# MY_beamControl_R.net
KiCad netlist of a schematic drawn in Altium Designer
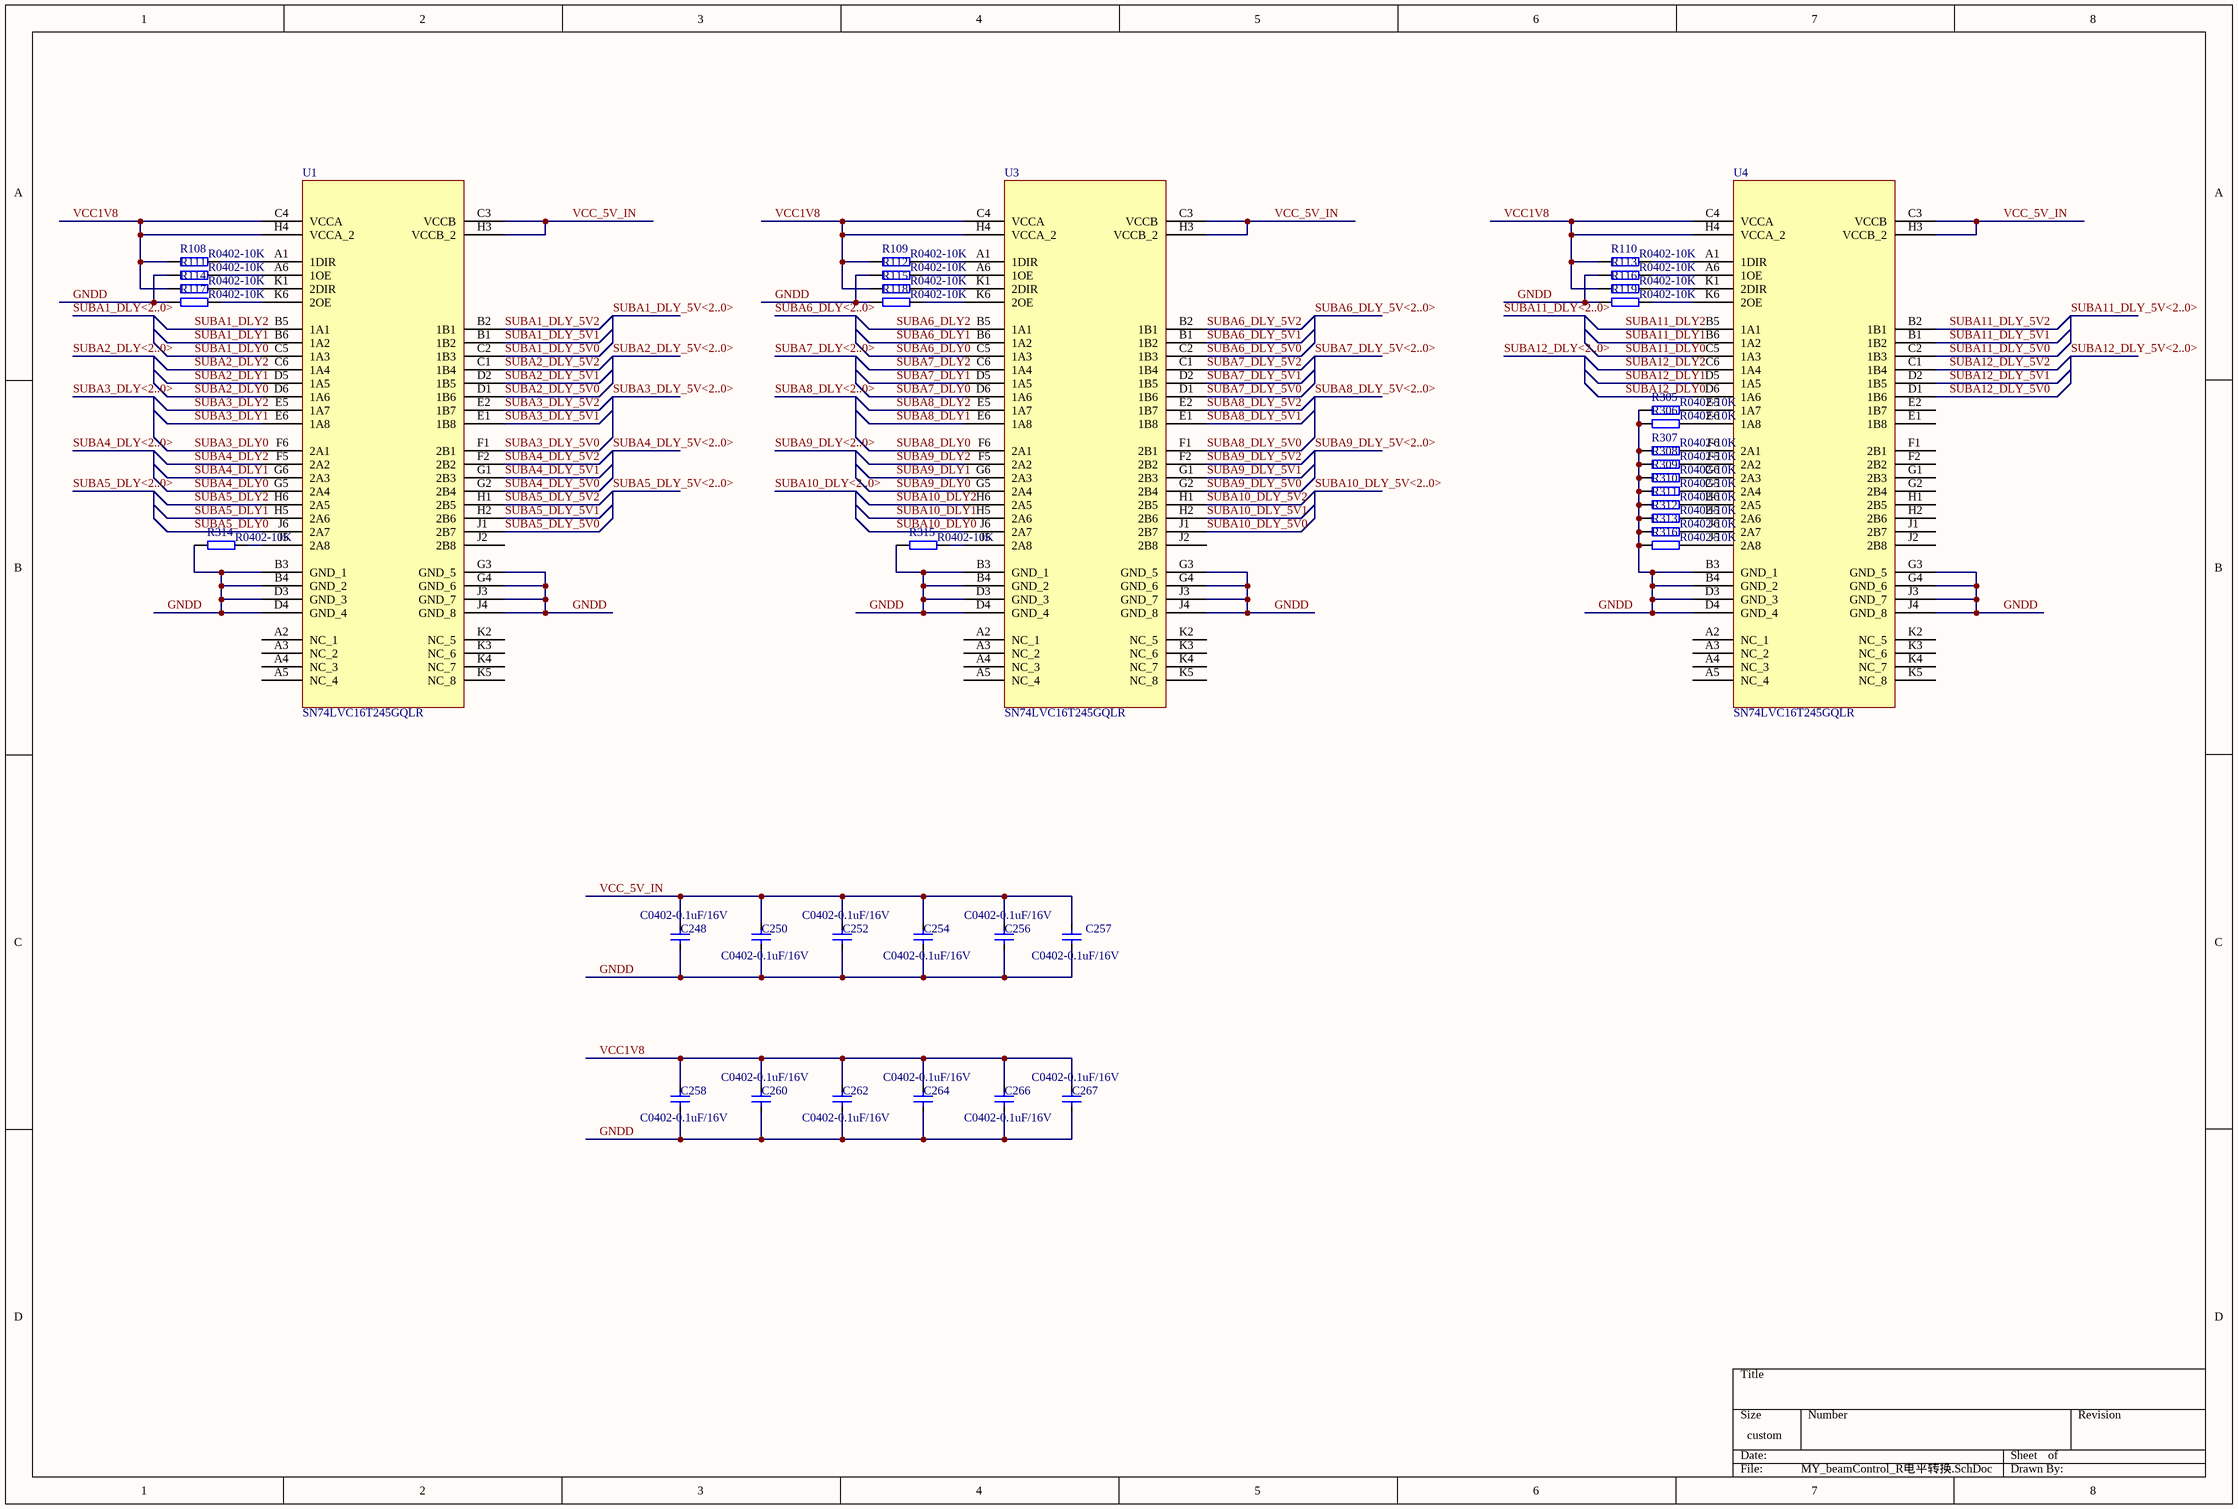
[diagram p0: MY_beamControl_R电平转换.SchDoc]

(export (version "E")
  (design (tool "Eeschema 10.0.6"))
  (components
    (comp (ref "C248")
      (value "C0402-0.1uF/16V")
      (footprint "C0402")
      (description "X7R")
      (fields (field (name "SCHEMATIC_PART") "CAP") (field (name "MANUFACTURER") "SAMSUNG"))
      (libsource (lib "Database_Libs1") (part "CAP"))
    )
    (comp (ref "C250")
      (value "C0402-0.1uF/16V")
      (footprint "C0402")
      (description "X7R")
      (fields (field (name "SCHEMATIC_PART") "CAP") (field (name "MANUFACTURER") "SAMSUNG"))
      (libsource (lib "Database_Libs1") (part "CAP"))
    )
    (comp (ref "C252")
      (value "C0402-0.1uF/16V")
      (footprint "C0402")
      (description "X7R")
      (fields (field (name "SCHEMATIC_PART") "CAP") (field (name "MANUFACTURER") "SAMSUNG"))
      (libsource (lib "Database_Libs1") (part "CAP"))
    )
    (comp (ref "C254")
      (value "C0402-0.1uF/16V")
      (footprint "C0402")
      (description "X7R")
      (fields (field (name "SCHEMATIC_PART") "CAP") (field (name "MANUFACTURER") "SAMSUNG"))
      (libsource (lib "Database_Libs1") (part "CAP"))
    )
    (comp (ref "C256")
      (value "C0402-0.1uF/16V")
      (footprint "C0402")
      (description "X7R")
      (fields (field (name "SCHEMATIC_PART") "CAP") (field (name "MANUFACTURER") "SAMSUNG"))
      (libsource (lib "Database_Libs1") (part "CAP"))
    )
    (comp (ref "C257")
      (value "C0402-0.1uF/16V")
      (footprint "C0402")
      (description "X7R")
      (fields (field (name "SCHEMATIC_PART") "CAP") (field (name "MANUFACTURER") "SAMSUNG"))
      (libsource (lib "Database_Libs1") (part "CAP"))
    )
    (comp (ref "C258")
      (value "C0402-0.1uF/16V")
      (footprint "C0402")
      (description "X7R")
      (fields (field (name "SCHEMATIC_PART") "CAP") (field (name "MANUFACTURER") "SAMSUNG"))
      (libsource (lib "Database_Libs1") (part "CAP"))
    )
    (comp (ref "C260")
      (value "C0402-0.1uF/16V")
      (footprint "C0402")
      (description "X7R")
      (fields (field (name "SCHEMATIC_PART") "CAP") (field (name "MANUFACTURER") "SAMSUNG"))
      (libsource (lib "Database_Libs1") (part "CAP"))
    )
    (comp (ref "C262")
      (value "C0402-0.1uF/16V")
      (footprint "C0402")
      (description "X7R")
      (fields (field (name "SCHEMATIC_PART") "CAP") (field (name "MANUFACTURER") "SAMSUNG"))
      (libsource (lib "Database_Libs1") (part "CAP"))
    )
    (comp (ref "C264")
      (value "C0402-0.1uF/16V")
      (footprint "C0402")
      (description "X7R")
      (fields (field (name "SCHEMATIC_PART") "CAP") (field (name "MANUFACTURER") "SAMSUNG"))
      (libsource (lib "Database_Libs1") (part "CAP"))
    )
    (comp (ref "C266")
      (value "C0402-0.1uF/16V")
      (footprint "C0402")
      (description "X7R")
      (fields (field (name "SCHEMATIC_PART") "CAP") (field (name "MANUFACTURER") "SAMSUNG"))
      (libsource (lib "Database_Libs1") (part "CAP"))
    )
    (comp (ref "C267")
      (value "C0402-0.1uF/16V")
      (footprint "C0402")
      (description "X7R")
      (fields (field (name "SCHEMATIC_PART") "CAP") (field (name "MANUFACTURER") "SAMSUNG"))
      (libsource (lib "Database_Libs1") (part "CAP"))
    )
    (comp (ref "R108")
      (value "R0402-10K")
      (footprint "R0402")
      (fields (field (name "SCHEMATIC_PART") "RES") (field (name "MANUFACTURER") "SAMSUNG"))
      (libsource (lib "Database_Libs1") (part "RES"))
    )
    (comp (ref "R109")
      (value "R0402-10K")
      (footprint "R0402")
      (fields (field (name "SCHEMATIC_PART") "RES") (field (name "MANUFACTURER") "SAMSUNG"))
      (libsource (lib "Database_Libs1") (part "RES"))
    )
    (comp (ref "R110")
      (value "R0402-10K")
      (footprint "R0402")
      (fields (field (name "SCHEMATIC_PART") "RES") (field (name "MANUFACTURER") "SAMSUNG"))
      (libsource (lib "Database_Libs1") (part "RES"))
    )
    (comp (ref "R111")
      (value "R0402-10K")
      (footprint "R0402")
      (fields (field (name "SCHEMATIC_PART") "RES") (field (name "MANUFACTURER") "SAMSUNG"))
      (libsource (lib "Database_Libs1") (part "RES"))
    )
    (comp (ref "R112")
      (value "R0402-10K")
      (footprint "R0402")
      (fields (field (name "SCHEMATIC_PART") "RES") (field (name "MANUFACTURER") "SAMSUNG"))
      (libsource (lib "Database_Libs1") (part "RES"))
    )
    (comp (ref "R113")
      (value "R0402-10K")
      (footprint "R0402")
      (fields (field (name "SCHEMATIC_PART") "RES") (field (name "MANUFACTURER") "SAMSUNG"))
      (libsource (lib "Database_Libs1") (part "RES"))
    )
    (comp (ref "R114")
      (value "R0402-10K")
      (footprint "R0402")
      (fields (field (name "SCHEMATIC_PART") "RES") (field (name "MANUFACTURER") "SAMSUNG"))
      (libsource (lib "Database_Libs1") (part "RES"))
    )
    (comp (ref "R115")
      (value "R0402-10K")
      (footprint "R0402")
      (fields (field (name "SCHEMATIC_PART") "RES") (field (name "MANUFACTURER") "SAMSUNG"))
      (libsource (lib "Database_Libs1") (part "RES"))
    )
    (comp (ref "R116")
      (value "R0402-10K")
      (footprint "R0402")
      (fields (field (name "SCHEMATIC_PART") "RES") (field (name "MANUFACTURER") "SAMSUNG"))
      (libsource (lib "Database_Libs1") (part "RES"))
    )
    (comp (ref "R117")
      (value "R0402-10K")
      (footprint "R0402")
      (fields (field (name "SCHEMATIC_PART") "RES") (field (name "MANUFACTURER") "SAMSUNG"))
      (libsource (lib "Database_Libs1") (part "RES"))
    )
    (comp (ref "R118")
      (value "R0402-10K")
      (footprint "R0402")
      (fields (field (name "SCHEMATIC_PART") "RES") (field (name "MANUFACTURER") "SAMSUNG"))
      (libsource (lib "Database_Libs1") (part "RES"))
    )
    (comp (ref "R119")
      (value "R0402-10K")
      (footprint "R0402")
      (fields (field (name "SCHEMATIC_PART") "RES") (field (name "MANUFACTURER") "SAMSUNG"))
      (libsource (lib "Database_Libs1") (part "RES"))
    )
    (comp (ref "R305")
      (value "R0402-10K")
      (footprint "R0402")
      (fields (field (name "SCHEMATIC_PART") "RES") (field (name "MANUFACTURER") "SAMSUNG"))
      (libsource (lib "Database_Libs1") (part "RES"))
    )
    (comp (ref "R306")
      (value "R0402-10K")
      (footprint "R0402")
      (fields (field (name "SCHEMATIC_PART") "RES") (field (name "MANUFACTURER") "SAMSUNG"))
      (libsource (lib "Database_Libs1") (part "RES"))
    )
    (comp (ref "R307")
      (value "R0402-10K")
      (footprint "R0402")
      (fields (field (name "SCHEMATIC_PART") "RES") (field (name "MANUFACTURER") "SAMSUNG"))
      (libsource (lib "Database_Libs1") (part "RES"))
    )
    (comp (ref "R308")
      (value "R0402-10K")
      (footprint "R0402")
      (fields (field (name "SCHEMATIC_PART") "RES") (field (name "MANUFACTURER") "SAMSUNG"))
      (libsource (lib "Database_Libs1") (part "RES"))
    )
    (comp (ref "R309")
      (value "R0402-10K")
      (footprint "R0402")
      (fields (field (name "SCHEMATIC_PART") "RES") (field (name "MANUFACTURER") "SAMSUNG"))
      (libsource (lib "Database_Libs1") (part "RES"))
    )
    (comp (ref "R310")
      (value "R0402-10K")
      (footprint "R0402")
      (fields (field (name "SCHEMATIC_PART") "RES") (field (name "MANUFACTURER") "SAMSUNG"))
      (libsource (lib "Database_Libs1") (part "RES"))
    )
    (comp (ref "R311")
      (value "R0402-10K")
      (footprint "R0402")
      (fields (field (name "SCHEMATIC_PART") "RES") (field (name "MANUFACTURER") "SAMSUNG"))
      (libsource (lib "Database_Libs1") (part "RES"))
    )
    (comp (ref "R312")
      (value "R0402-10K")
      (footprint "R0402")
      (fields (field (name "SCHEMATIC_PART") "RES") (field (name "MANUFACTURER") "SAMSUNG"))
      (libsource (lib "Database_Libs1") (part "RES"))
    )
    (comp (ref "R313")
      (value "R0402-10K")
      (footprint "R0402")
      (fields (field (name "SCHEMATIC_PART") "RES") (field (name "MANUFACTURER") "SAMSUNG"))
      (libsource (lib "Database_Libs1") (part "RES"))
    )
    (comp (ref "R314")
      (value "R0402-10K")
      (footprint "R0402")
      (fields (field (name "SCHEMATIC_PART") "RES") (field (name "MANUFACTURER") "SAMSUNG"))
      (libsource (lib "Database_Libs1") (part "RES"))
    )
    (comp (ref "R315")
      (value "R0402-10K")
      (footprint "R0402")
      (fields (field (name "SCHEMATIC_PART") "RES") (field (name "MANUFACTURER") "SAMSUNG"))
      (libsource (lib "Database_Libs1") (part "RES"))
    )
    (comp (ref "R316")
      (value "R0402-10K")
      (footprint "R0402")
      (fields (field (name "SCHEMATIC_PART") "RES") (field (name "MANUFACTURER") "SAMSUNG"))
      (libsource (lib "Database_Libs1") (part "RES"))
    )
    (comp (ref "U1")
      (value "SN74LVC16T245GQLR")
      (footprint "BGA-56")
      (libsource (lib "SCHLIB1") (part "SN74LVC16T245"))
    )
    (comp (ref "U3")
      (value "SN74LVC16T245GQLR")
      (footprint "BGA-56")
      (libsource (lib "SCHLIB1") (part "SN74LVC16T245"))
    )
    (comp (ref "U4")
      (value "SN74LVC16T245GQLR")
      (footprint "BGA-56")
      (libsource (lib "SCHLIB1") (part "SN74LVC16T245"))
    )
  )
  (nets
    (net (code "25") (name "/GNDD") (class "Default")
      (node (ref "C248") (pin "2") (pinfunction "2_2") (pintype "passive"))
      (node (ref "C250") (pin "2") (pinfunction "2_2") (pintype "passive"))
      (node (ref "C252") (pin "2") (pinfunction "2_2") (pintype "passive"))
      (node (ref "C254") (pin "2") (pinfunction "2_2") (pintype "passive"))
      (node (ref "C256") (pin "2") (pinfunction "2_2") (pintype "passive"))
      (node (ref "C257") (pin "2") (pinfunction "2_2") (pintype "passive"))
      (node (ref "C258") (pin "2") (pinfunction "2_2") (pintype "passive"))
      (node (ref "C260") (pin "2") (pinfunction "2_2") (pintype "passive"))
      (node (ref "C262") (pin "2") (pinfunction "2_2") (pintype "passive"))
      (node (ref "C264") (pin "2") (pinfunction "2_2") (pintype "passive"))
      (node (ref "C266") (pin "2") (pinfunction "2_2") (pintype "passive"))
      (node (ref "C267") (pin "2") (pinfunction "2_2") (pintype "passive"))
      (node (ref "R111") (pin "1") (pintype "passive"))
      (node (ref "R112") (pin "1") (pintype "passive"))
      (node (ref "R113") (pin "1") (pintype "passive"))
      (node (ref "R117") (pin "1") (pintype "passive"))
      (node (ref "R118") (pin "1") (pintype "passive"))
      (node (ref "R119") (pin "1") (pintype "passive"))
      (node (ref "R305") (pin "1") (pintype "passive"))
      (node (ref "R306") (pin "1") (pintype "passive"))
      (node (ref "R307") (pin "1") (pintype "passive"))
      (node (ref "R308") (pin "1") (pintype "passive"))
      (node (ref "R309") (pin "1") (pintype "passive"))
      (node (ref "R310") (pin "1") (pintype "passive"))
      (node (ref "R311") (pin "1") (pintype "passive"))
      (node (ref "R312") (pin "1") (pintype "passive"))
      (node (ref "R313") (pin "1") (pintype "passive"))
      (node (ref "R314") (pin "1") (pintype "passive"))
      (node (ref "R315") (pin "1") (pintype "passive"))
      (node (ref "R316") (pin "1") (pintype "passive"))
      (node (ref "U1") (pin "B3") (pinfunction "GND_1_B3") (pintype "passive"))
      (node (ref "U1") (pin "B4") (pinfunction "GND_2_B4") (pintype "passive"))
      (node (ref "U1") (pin "D3") (pinfunction "GND_3_D3") (pintype "passive"))
      (node (ref "U1") (pin "D4") (pinfunction "GND_4_D4") (pintype "passive"))
      (node (ref "U1") (pin "G3") (pinfunction "GND_5_G3") (pintype "passive"))
      (node (ref "U1") (pin "G4") (pinfunction "GND_6_G4") (pintype "passive"))
      (node (ref "U1") (pin "J3") (pinfunction "GND_7_J3") (pintype "passive"))
      (node (ref "U1") (pin "J4") (pinfunction "GND_8_J4") (pintype "passive"))
      (node (ref "U3") (pin "B3") (pinfunction "GND_1_B3") (pintype "passive"))
      (node (ref "U3") (pin "B4") (pinfunction "GND_2_B4") (pintype "passive"))
      (node (ref "U3") (pin "D3") (pinfunction "GND_3_D3") (pintype "passive"))
      (node (ref "U3") (pin "D4") (pinfunction "GND_4_D4") (pintype "passive"))
      (node (ref "U3") (pin "G3") (pinfunction "GND_5_G3") (pintype "passive"))
      (node (ref "U3") (pin "G4") (pinfunction "GND_6_G4") (pintype "passive"))
      (node (ref "U3") (pin "J3") (pinfunction "GND_7_J3") (pintype "passive"))
      (node (ref "U3") (pin "J4") (pinfunction "GND_8_J4") (pintype "passive"))
      (node (ref "U4") (pin "B3") (pinfunction "GND_1_B3") (pintype "passive"))
      (node (ref "U4") (pin "B4") (pinfunction "GND_2_B4") (pintype "passive"))
      (node (ref "U4") (pin "D3") (pinfunction "GND_3_D3") (pintype "passive"))
      (node (ref "U4") (pin "D4") (pinfunction "GND_4_D4") (pintype "passive"))
      (node (ref "U4") (pin "G3") (pinfunction "GND_5_G3") (pintype "passive"))
      (node (ref "U4") (pin "G4") (pinfunction "GND_6_G4") (pintype "passive"))
      (node (ref "U4") (pin "J3") (pinfunction "GND_7_J3") (pintype "passive"))
      (node (ref "U4") (pin "J4") (pinfunction "GND_8_J4") (pintype "passive"))
    )
    (net (code "26") (name "/SUBA1_DLY0") (class "Default")
      (node (ref "U1") (pin "C5") (pinfunction "1A3_C5") (pintype "passive"))
    )
    (net (code "27") (name "/SUBA1_DLY1") (class "Default")
      (node (ref "U1") (pin "B6") (pinfunction "1A2_B6") (pintype "passive"))
    )
    (net (code "28") (name "/SUBA1_DLY2") (class "Default")
      (node (ref "U1") (pin "B5") (pinfunction "1A1_B5") (pintype "passive"))
    )
    (net (code "29") (name "/SUBA1_DLY_5V0") (class "Default")
      (node (ref "U1") (pin "C2") (pinfunction "1B3_C2") (pintype "passive"))
    )
    (net (code "30") (name "/SUBA1_DLY_5V1") (class "Default")
      (node (ref "U1") (pin "B1") (pinfunction "1B2_B1") (pintype "passive"))
    )
    (net (code "31") (name "/SUBA1_DLY_5V2") (class "Default")
      (node (ref "U1") (pin "B2") (pinfunction "1B1_B2") (pintype "passive"))
    )
    (net (code "32") (name "/SUBA2_DLY0") (class "Default")
      (node (ref "U1") (pin "D6") (pinfunction "1A6_D6") (pintype "passive"))
    )
    (net (code "33") (name "/SUBA2_DLY1") (class "Default")
      (node (ref "U1") (pin "D5") (pinfunction "1A5_D5") (pintype "passive"))
    )
    (net (code "34") (name "/SUBA2_DLY2") (class "Default")
      (node (ref "U1") (pin "C6") (pinfunction "1A4_C6") (pintype "passive"))
    )
    (net (code "35") (name "/SUBA2_DLY_5V0") (class "Default")
      (node (ref "U1") (pin "D1") (pinfunction "1B6_D1") (pintype "passive"))
    )
    (net (code "36") (name "/SUBA2_DLY_5V1") (class "Default")
      (node (ref "U1") (pin "D2") (pinfunction "1B5_D2") (pintype "passive"))
    )
    (net (code "37") (name "/SUBA2_DLY_5V2") (class "Default")
      (node (ref "U1") (pin "C1") (pinfunction "1B4_C1") (pintype "passive"))
    )
    (net (code "38") (name "/SUBA3_DLY0") (class "Default")
      (node (ref "U1") (pin "F6") (pinfunction "2A1_F6") (pintype "passive"))
    )
    (net (code "39") (name "/SUBA3_DLY1") (class "Default")
      (node (ref "U1") (pin "E6") (pinfunction "1A8_E6") (pintype "passive"))
    )
    (net (code "40") (name "/SUBA3_DLY2") (class "Default")
      (node (ref "U1") (pin "E5") (pinfunction "1A7_E5") (pintype "passive"))
    )
    (net (code "41") (name "/SUBA3_DLY_5V0") (class "Default")
      (node (ref "U1") (pin "F1") (pinfunction "2B1_F1") (pintype "passive"))
    )
    (net (code "42") (name "/SUBA3_DLY_5V1") (class "Default")
      (node (ref "U1") (pin "E1") (pinfunction "1B8_E1") (pintype "passive"))
    )
    (net (code "43") (name "/SUBA3_DLY_5V2") (class "Default")
      (node (ref "U1") (pin "E2") (pinfunction "1B7_E2") (pintype "passive"))
    )
    (net (code "44") (name "/SUBA4_DLY0") (class "Default")
      (node (ref "U1") (pin "G5") (pinfunction "2A4_G5") (pintype "passive"))
    )
    (net (code "45") (name "/SUBA4_DLY1") (class "Default")
      (node (ref "U1") (pin "G6") (pinfunction "2A3_G6") (pintype "passive"))
    )
    (net (code "46") (name "/SUBA4_DLY2") (class "Default")
      (node (ref "U1") (pin "F5") (pinfunction "2A2_F5") (pintype "passive"))
    )
    (net (code "47") (name "/SUBA4_DLY_5V0") (class "Default")
      (node (ref "U1") (pin "G2") (pinfunction "2B4_G2") (pintype "passive"))
    )
    (net (code "48") (name "/SUBA4_DLY_5V1") (class "Default")
      (node (ref "U1") (pin "G1") (pinfunction "2B3_G1") (pintype "passive"))
    )
    (net (code "49") (name "/SUBA4_DLY_5V2") (class "Default")
      (node (ref "U1") (pin "F2") (pinfunction "2B2_F2") (pintype "passive"))
    )
    (net (code "50") (name "/SUBA5_DLY0") (class "Default")
      (node (ref "U1") (pin "J6") (pinfunction "2A7_J6") (pintype "passive"))
    )
    (net (code "51") (name "/SUBA5_DLY1") (class "Default")
      (node (ref "U1") (pin "H5") (pinfunction "2A6_H5") (pintype "passive"))
    )
    (net (code "52") (name "/SUBA5_DLY2") (class "Default")
      (node (ref "U1") (pin "H6") (pinfunction "2A5_H6") (pintype "passive"))
    )
    (net (code "53") (name "/SUBA5_DLY_5V0") (class "Default")
      (node (ref "U1") (pin "J1") (pinfunction "2B7_J1") (pintype "passive"))
    )
    (net (code "54") (name "/SUBA5_DLY_5V1") (class "Default")
      (node (ref "U1") (pin "H2") (pinfunction "2B6_H2") (pintype "passive"))
    )
    (net (code "55") (name "/SUBA5_DLY_5V2") (class "Default")
      (node (ref "U1") (pin "H1") (pinfunction "2B5_H1") (pintype "passive"))
    )
    (net (code "56") (name "/SUBA6_DLY0") (class "Default")
      (node (ref "U3") (pin "C5") (pinfunction "1A3_C5") (pintype "passive"))
    )
    (net (code "57") (name "/SUBA6_DLY1") (class "Default")
      (node (ref "U3") (pin "B6") (pinfunction "1A2_B6") (pintype "passive"))
    )
    (net (code "58") (name "/SUBA6_DLY2") (class "Default")
      (node (ref "U3") (pin "B5") (pinfunction "1A1_B5") (pintype "passive"))
    )
    (net (code "59") (name "/SUBA6_DLY_5V0") (class "Default")
      (node (ref "U3") (pin "C2") (pinfunction "1B3_C2") (pintype "passive"))
    )
    (net (code "60") (name "/SUBA6_DLY_5V1") (class "Default")
      (node (ref "U3") (pin "B1") (pinfunction "1B2_B1") (pintype "passive"))
    )
    (net (code "61") (name "/SUBA6_DLY_5V2") (class "Default")
      (node (ref "U3") (pin "B2") (pinfunction "1B1_B2") (pintype "passive"))
    )
    (net (code "62") (name "/SUBA7_DLY0") (class "Default")
      (node (ref "U3") (pin "D6") (pinfunction "1A6_D6") (pintype "passive"))
    )
    (net (code "63") (name "/SUBA7_DLY1") (class "Default")
      (node (ref "U3") (pin "D5") (pinfunction "1A5_D5") (pintype "passive"))
    )
    (net (code "64") (name "/SUBA7_DLY2") (class "Default")
      (node (ref "U3") (pin "C6") (pinfunction "1A4_C6") (pintype "passive"))
    )
    (net (code "65") (name "/SUBA7_DLY_5V0") (class "Default")
      (node (ref "U3") (pin "D1") (pinfunction "1B6_D1") (pintype "passive"))
    )
    (net (code "66") (name "/SUBA7_DLY_5V1") (class "Default")
      (node (ref "U3") (pin "D2") (pinfunction "1B5_D2") (pintype "passive"))
    )
    (net (code "67") (name "/SUBA7_DLY_5V2") (class "Default")
      (node (ref "U3") (pin "C1") (pinfunction "1B4_C1") (pintype "passive"))
    )
    (net (code "68") (name "/SUBA8_DLY0") (class "Default")
      (node (ref "U3") (pin "F6") (pinfunction "2A1_F6") (pintype "passive"))
    )
    (net (code "69") (name "/SUBA8_DLY1") (class "Default")
      (node (ref "U3") (pin "E6") (pinfunction "1A8_E6") (pintype "passive"))
    )
    (net (code "70") (name "/SUBA8_DLY2") (class "Default")
      (node (ref "U3") (pin "E5") (pinfunction "1A7_E5") (pintype "passive"))
    )
    (net (code "71") (name "/SUBA8_DLY_5V0") (class "Default")
      (node (ref "U3") (pin "F1") (pinfunction "2B1_F1") (pintype "passive"))
    )
    (net (code "72") (name "/SUBA8_DLY_5V1") (class "Default")
      (node (ref "U3") (pin "E1") (pinfunction "1B8_E1") (pintype "passive"))
    )
    (net (code "73") (name "/SUBA8_DLY_5V2") (class "Default")
      (node (ref "U3") (pin "E2") (pinfunction "1B7_E2") (pintype "passive"))
    )
    (net (code "74") (name "/SUBA9_DLY0") (class "Default")
      (node (ref "U3") (pin "G5") (pinfunction "2A4_G5") (pintype "passive"))
    )
    (net (code "75") (name "/SUBA9_DLY1") (class "Default")
      (node (ref "U3") (pin "G6") (pinfunction "2A3_G6") (pintype "passive"))
    )
    (net (code "76") (name "/SUBA9_DLY2") (class "Default")
      (node (ref "U3") (pin "F5") (pinfunction "2A2_F5") (pintype "passive"))
    )
    (net (code "77") (name "/SUBA9_DLY_5V0") (class "Default")
      (node (ref "U3") (pin "G2") (pinfunction "2B4_G2") (pintype "passive"))
    )
    (net (code "78") (name "/SUBA9_DLY_5V1") (class "Default")
      (node (ref "U3") (pin "G1") (pinfunction "2B3_G1") (pintype "passive"))
    )
    (net (code "79") (name "/SUBA9_DLY_5V2") (class "Default")
      (node (ref "U3") (pin "F2") (pinfunction "2B2_F2") (pintype "passive"))
    )
    (net (code "80") (name "/SUBA10_DLY0") (class "Default")
      (node (ref "U3") (pin "J6") (pinfunction "2A7_J6") (pintype "passive"))
    )
    (net (code "81") (name "/SUBA10_DLY1") (class "Default")
      (node (ref "U3") (pin "H5") (pinfunction "2A6_H5") (pintype "passive"))
    )
    (net (code "82") (name "/SUBA10_DLY2") (class "Default")
      (node (ref "U3") (pin "H6") (pinfunction "2A5_H6") (pintype "passive"))
    )
    (net (code "83") (name "/SUBA10_DLY_5V0") (class "Default")
      (node (ref "U3") (pin "J1") (pinfunction "2B7_J1") (pintype "passive"))
    )
    (net (code "84") (name "/SUBA10_DLY_5V1") (class "Default")
      (node (ref "U3") (pin "H2") (pinfunction "2B6_H2") (pintype "passive"))
    )
    (net (code "85") (name "/SUBA10_DLY_5V2") (class "Default")
      (node (ref "U3") (pin "H1") (pinfunction "2B5_H1") (pintype "passive"))
    )
    (net (code "86") (name "/SUBA11_DLY0") (class "Default")
      (node (ref "U4") (pin "C5") (pinfunction "1A3_C5") (pintype "passive"))
    )
    (net (code "87") (name "/SUBA11_DLY1") (class "Default")
      (node (ref "U4") (pin "B6") (pinfunction "1A2_B6") (pintype "passive"))
    )
    (net (code "88") (name "/SUBA11_DLY2") (class "Default")
      (node (ref "U4") (pin "B5") (pinfunction "1A1_B5") (pintype "passive"))
    )
    (net (code "89") (name "/SUBA11_DLY_5V0") (class "Default")
      (node (ref "U4") (pin "C2") (pinfunction "1B3_C2") (pintype "passive"))
    )
    (net (code "90") (name "/SUBA11_DLY_5V1") (class "Default")
      (node (ref "U4") (pin "B1") (pinfunction "1B2_B1") (pintype "passive"))
    )
    (net (code "91") (name "/SUBA11_DLY_5V2") (class "Default")
      (node (ref "U4") (pin "B2") (pinfunction "1B1_B2") (pintype "passive"))
    )
    (net (code "92") (name "/SUBA12_DLY0") (class "Default")
      (node (ref "U4") (pin "D6") (pinfunction "1A6_D6") (pintype "passive"))
    )
    (net (code "93") (name "/SUBA12_DLY1") (class "Default")
      (node (ref "U4") (pin "D5") (pinfunction "1A5_D5") (pintype "passive"))
    )
    (net (code "94") (name "/SUBA12_DLY2") (class "Default")
      (node (ref "U4") (pin "C6") (pinfunction "1A4_C6") (pintype "passive"))
    )
    (net (code "95") (name "/SUBA12_DLY_5V0") (class "Default")
      (node (ref "U4") (pin "D1") (pinfunction "1B6_D1") (pintype "passive"))
    )
    (net (code "96") (name "/SUBA12_DLY_5V1") (class "Default")
      (node (ref "U4") (pin "D2") (pinfunction "1B5_D2") (pintype "passive"))
    )
    (net (code "97") (name "/SUBA12_DLY_5V2") (class "Default")
      (node (ref "U4") (pin "C1") (pinfunction "1B4_C1") (pintype "passive"))
    )
    (net (code "98") (name "/VCC1V8") (class "Default")
      (node (ref "C258") (pin "1") (pinfunction "1_1") (pintype "passive"))
      (node (ref "C260") (pin "1") (pinfunction "1_1") (pintype "passive"))
      (node (ref "C262") (pin "1") (pinfunction "1_1") (pintype "passive"))
      (node (ref "C264") (pin "1") (pinfunction "1_1") (pintype "passive"))
      (node (ref "C266") (pin "1") (pinfunction "1_1") (pintype "passive"))
      (node (ref "C267") (pin "1") (pinfunction "1_1") (pintype "passive"))
      (node (ref "R108") (pin "1") (pintype "passive"))
      (node (ref "R109") (pin "1") (pintype "passive"))
      (node (ref "R110") (pin "1") (pintype "passive"))
      (node (ref "R114") (pin "1") (pintype "passive"))
      (node (ref "R115") (pin "1") (pintype "passive"))
      (node (ref "R116") (pin "1") (pintype "passive"))
      (node (ref "U1") (pin "C4") (pinfunction "VCCA_C4") (pintype "passive"))
      (node (ref "U1") (pin "H4") (pinfunction "VCCA_2_H4") (pintype "passive"))
      (node (ref "U3") (pin "C4") (pinfunction "VCCA_C4") (pintype "passive"))
      (node (ref "U3") (pin "H4") (pinfunction "VCCA_2_H4") (pintype "passive"))
      (node (ref "U4") (pin "C4") (pinfunction "VCCA_C4") (pintype "passive"))
      (node (ref "U4") (pin "H4") (pinfunction "VCCA_2_H4") (pintype "passive"))
    )
    (net (code "99") (name "/VCC_5V_IN") (class "Default")
      (node (ref "C248") (pin "1") (pinfunction "1_1") (pintype "passive"))
      (node (ref "C250") (pin "1") (pinfunction "1_1") (pintype "passive"))
      (node (ref "C252") (pin "1") (pinfunction "1_1") (pintype "passive"))
      (node (ref "C254") (pin "1") (pinfunction "1_1") (pintype "passive"))
      (node (ref "C256") (pin "1") (pinfunction "1_1") (pintype "passive"))
      (node (ref "C257") (pin "1") (pinfunction "1_1") (pintype "passive"))
      (node (ref "U1") (pin "C3") (pinfunction "VCCB_C3") (pintype "passive"))
      (node (ref "U1") (pin "H3") (pinfunction "VCCB_2_H3") (pintype "passive"))
      (node (ref "U3") (pin "C3") (pinfunction "VCCB_C3") (pintype "passive"))
      (node (ref "U3") (pin "H3") (pinfunction "VCCB_2_H3") (pintype "passive"))
      (node (ref "U4") (pin "C3") (pinfunction "VCCB_C3") (pintype "passive"))
      (node (ref "U4") (pin "H3") (pinfunction "VCCB_2_H3") (pintype "passive"))
    )
    (net (code "124") (name "Net-(U1-1DIR)") (class "Default")
      (node (ref "R108") (pin "2") (pintype "passive"))
      (node (ref "U1") (pin "A1") (pinfunction "1DIR_A1") (pintype "passive"))
    )
    (net (code "125") (name "Net-(U1-1OE)") (class "Default")
      (node (ref "R111") (pin "2") (pintype "passive"))
      (node (ref "U1") (pin "A6") (pinfunction "1OE_A6") (pintype "passive"))
    )
    (net (code "126") (name "Net-(U1-2A8)") (class "Default")
      (node (ref "R314") (pin "2") (pintype "passive"))
      (node (ref "U1") (pin "J5") (pinfunction "2A8_J5") (pintype "passive"))
    )
    (net (code "127") (name "Net-(U1-2DIR)") (class "Default")
      (node (ref "R114") (pin "2") (pintype "passive"))
      (node (ref "U1") (pin "K1") (pinfunction "2DIR_K1") (pintype "passive"))
    )
    (net (code "128") (name "Net-(U1-2OE)") (class "Default")
      (node (ref "R117") (pin "2") (pintype "passive"))
      (node (ref "U1") (pin "K6") (pinfunction "2OE_K6") (pintype "passive"))
    )
    (net (code "129") (name "Net-(U3-1DIR)") (class "Default")
      (node (ref "R109") (pin "2") (pintype "passive"))
      (node (ref "U3") (pin "A1") (pinfunction "1DIR_A1") (pintype "passive"))
    )
    (net (code "130") (name "Net-(U3-1OE)") (class "Default")
      (node (ref "R112") (pin "2") (pintype "passive"))
      (node (ref "U3") (pin "A6") (pinfunction "1OE_A6") (pintype "passive"))
    )
    (net (code "131") (name "Net-(U3-2A8)") (class "Default")
      (node (ref "R315") (pin "2") (pintype "passive"))
      (node (ref "U3") (pin "J5") (pinfunction "2A8_J5") (pintype "passive"))
    )
    (net (code "132") (name "Net-(U3-2DIR)") (class "Default")
      (node (ref "R115") (pin "2") (pintype "passive"))
      (node (ref "U3") (pin "K1") (pinfunction "2DIR_K1") (pintype "passive"))
    )
    (net (code "133") (name "Net-(U3-2OE)") (class "Default")
      (node (ref "R118") (pin "2") (pintype "passive"))
      (node (ref "U3") (pin "K6") (pinfunction "2OE_K6") (pintype "passive"))
    )
    (net (code "134") (name "Net-(U4-1A7)") (class "Default")
      (node (ref "R305") (pin "2") (pintype "passive"))
      (node (ref "U4") (pin "E5") (pinfunction "1A7_E5") (pintype "passive"))
    )
    (net (code "135") (name "Net-(U4-1A8)") (class "Default")
      (node (ref "R306") (pin "2") (pintype "passive"))
      (node (ref "U4") (pin "E6") (pinfunction "1A8_E6") (pintype "passive"))
    )
    (net (code "136") (name "Net-(U4-1DIR)") (class "Default")
      (node (ref "R110") (pin "2") (pintype "passive"))
      (node (ref "U4") (pin "A1") (pinfunction "1DIR_A1") (pintype "passive"))
    )
    (net (code "137") (name "Net-(U4-1OE)") (class "Default")
      (node (ref "R113") (pin "2") (pintype "passive"))
      (node (ref "U4") (pin "A6") (pinfunction "1OE_A6") (pintype "passive"))
    )
    (net (code "138") (name "Net-(U4-2A1)") (class "Default")
      (node (ref "R307") (pin "2") (pintype "passive"))
      (node (ref "U4") (pin "F6") (pinfunction "2A1_F6") (pintype "passive"))
    )
    (net (code "139") (name "Net-(U4-2A2)") (class "Default")
      (node (ref "R308") (pin "2") (pintype "passive"))
      (node (ref "U4") (pin "F5") (pinfunction "2A2_F5") (pintype "passive"))
    )
    (net (code "140") (name "Net-(U4-2A3)") (class "Default")
      (node (ref "R309") (pin "2") (pintype "passive"))
      (node (ref "U4") (pin "G6") (pinfunction "2A3_G6") (pintype "passive"))
    )
    (net (code "141") (name "Net-(U4-2A4)") (class "Default")
      (node (ref "R310") (pin "2") (pintype "passive"))
      (node (ref "U4") (pin "G5") (pinfunction "2A4_G5") (pintype "passive"))
    )
    (net (code "142") (name "Net-(U4-2A5)") (class "Default")
      (node (ref "R311") (pin "2") (pintype "passive"))
      (node (ref "U4") (pin "H6") (pinfunction "2A5_H6") (pintype "passive"))
    )
    (net (code "143") (name "Net-(U4-2A6)") (class "Default")
      (node (ref "R312") (pin "2") (pintype "passive"))
      (node (ref "U4") (pin "H5") (pinfunction "2A6_H5") (pintype "passive"))
    )
    (net (code "144") (name "Net-(U4-2A7)") (class "Default")
      (node (ref "R313") (pin "2") (pintype "passive"))
      (node (ref "U4") (pin "J6") (pinfunction "2A7_J6") (pintype "passive"))
    )
    (net (code "145") (name "Net-(U4-2A8)") (class "Default")
      (node (ref "R316") (pin "2") (pintype "passive"))
      (node (ref "U4") (pin "J5") (pinfunction "2A8_J5") (pintype "passive"))
    )
    (net (code "146") (name "Net-(U4-2DIR)") (class "Default")
      (node (ref "R116") (pin "2") (pintype "passive"))
      (node (ref "U4") (pin "K1") (pinfunction "2DIR_K1") (pintype "passive"))
    )
    (net (code "147") (name "Net-(U4-2OE)") (class "Default")
      (node (ref "R119") (pin "2") (pintype "passive"))
      (node (ref "U4") (pin "K6") (pinfunction "2OE_K6") (pintype "passive"))
    )
    (net (code "148") (name "unconnected-(U1-2B8-PadJ2)") (class "Default")
      (node (ref "U1") (pin "J2") (pinfunction "2B8_J2") (pintype "passive"))
    )
    (net (code "149") (name "unconnected-(U1-NC_1-PadA2)") (class "Default")
      (node (ref "U1") (pin "A2") (pinfunction "NC_1_A2") (pintype "passive"))
    )
    (net (code "150") (name "unconnected-(U1-NC_2-PadA3)") (class "Default")
      (node (ref "U1") (pin "A3") (pinfunction "NC_2_A3") (pintype "passive"))
    )
    (net (code "151") (name "unconnected-(U1-NC_3-PadA4)") (class "Default")
      (node (ref "U1") (pin "A4") (pinfunction "NC_3_A4") (pintype "passive"))
    )
    (net (code "152") (name "unconnected-(U1-NC_4-PadA5)") (class "Default")
      (node (ref "U1") (pin "A5") (pinfunction "NC_4_A5") (pintype "passive"))
    )
    (net (code "153") (name "unconnected-(U1-NC_5-PadK2)") (class "Default")
      (node (ref "U1") (pin "K2") (pinfunction "NC_5_K2") (pintype "passive"))
    )
    (net (code "154") (name "unconnected-(U1-NC_6-PadK3)") (class "Default")
      (node (ref "U1") (pin "K3") (pinfunction "NC_6_K3") (pintype "passive"))
    )
    (net (code "155") (name "unconnected-(U1-NC_7-PadK4)") (class "Default")
      (node (ref "U1") (pin "K4") (pinfunction "NC_7_K4") (pintype "passive"))
    )
    (net (code "156") (name "unconnected-(U1-NC_8-PadK5)") (class "Default")
      (node (ref "U1") (pin "K5") (pinfunction "NC_8_K5") (pintype "passive"))
    )
    (net (code "157") (name "unconnected-(U3-2B8-PadJ2)") (class "Default")
      (node (ref "U3") (pin "J2") (pinfunction "2B8_J2") (pintype "passive"))
    )
    (net (code "158") (name "unconnected-(U3-NC_1-PadA2)") (class "Default")
      (node (ref "U3") (pin "A2") (pinfunction "NC_1_A2") (pintype "passive"))
    )
    (net (code "159") (name "unconnected-(U3-NC_2-PadA3)") (class "Default")
      (node (ref "U3") (pin "A3") (pinfunction "NC_2_A3") (pintype "passive"))
    )
    (net (code "160") (name "unconnected-(U3-NC_3-PadA4)") (class "Default")
      (node (ref "U3") (pin "A4") (pinfunction "NC_3_A4") (pintype "passive"))
    )
    (net (code "161") (name "unconnected-(U3-NC_4-PadA5)") (class "Default")
      (node (ref "U3") (pin "A5") (pinfunction "NC_4_A5") (pintype "passive"))
    )
    (net (code "162") (name "unconnected-(U3-NC_5-PadK2)") (class "Default")
      (node (ref "U3") (pin "K2") (pinfunction "NC_5_K2") (pintype "passive"))
    )
    (net (code "163") (name "unconnected-(U3-NC_6-PadK3)") (class "Default")
      (node (ref "U3") (pin "K3") (pinfunction "NC_6_K3") (pintype "passive"))
    )
    (net (code "164") (name "unconnected-(U3-NC_7-PadK4)") (class "Default")
      (node (ref "U3") (pin "K4") (pinfunction "NC_7_K4") (pintype "passive"))
    )
    (net (code "165") (name "unconnected-(U3-NC_8-PadK5)") (class "Default")
      (node (ref "U3") (pin "K5") (pinfunction "NC_8_K5") (pintype "passive"))
    )
    (net (code "166") (name "unconnected-(U4-1B7-PadE2)") (class "Default")
      (node (ref "U4") (pin "E2") (pinfunction "1B7_E2") (pintype "passive"))
    )
    (net (code "167") (name "unconnected-(U4-1B8-PadE1)") (class "Default")
      (node (ref "U4") (pin "E1") (pinfunction "1B8_E1") (pintype "passive"))
    )
    (net (code "168") (name "unconnected-(U4-2B1-PadF1)") (class "Default")
      (node (ref "U4") (pin "F1") (pinfunction "2B1_F1") (pintype "passive"))
    )
    (net (code "169") (name "unconnected-(U4-2B2-PadF2)") (class "Default")
      (node (ref "U4") (pin "F2") (pinfunction "2B2_F2") (pintype "passive"))
    )
    (net (code "170") (name "unconnected-(U4-2B3-PadG1)") (class "Default")
      (node (ref "U4") (pin "G1") (pinfunction "2B3_G1") (pintype "passive"))
    )
    (net (code "171") (name "unconnected-(U4-2B4-PadG2)") (class "Default")
      (node (ref "U4") (pin "G2") (pinfunction "2B4_G2") (pintype "passive"))
    )
    (net (code "172") (name "unconnected-(U4-2B5-PadH1)") (class "Default")
      (node (ref "U4") (pin "H1") (pinfunction "2B5_H1") (pintype "passive"))
    )
    (net (code "173") (name "unconnected-(U4-2B6-PadH2)") (class "Default")
      (node (ref "U4") (pin "H2") (pinfunction "2B6_H2") (pintype "passive"))
    )
    (net (code "174") (name "unconnected-(U4-2B7-PadJ1)") (class "Default")
      (node (ref "U4") (pin "J1") (pinfunction "2B7_J1") (pintype "passive"))
    )
    (net (code "175") (name "unconnected-(U4-2B8-PadJ2)") (class "Default")
      (node (ref "U4") (pin "J2") (pinfunction "2B8_J2") (pintype "passive"))
    )
    (net (code "176") (name "unconnected-(U4-NC_1-PadA2)") (class "Default")
      (node (ref "U4") (pin "A2") (pinfunction "NC_1_A2") (pintype "passive"))
    )
    (net (code "177") (name "unconnected-(U4-NC_2-PadA3)") (class "Default")
      (node (ref "U4") (pin "A3") (pinfunction "NC_2_A3") (pintype "passive"))
    )
    (net (code "178") (name "unconnected-(U4-NC_3-PadA4)") (class "Default")
      (node (ref "U4") (pin "A4") (pinfunction "NC_3_A4") (pintype "passive"))
    )
    (net (code "179") (name "unconnected-(U4-NC_4-PadA5)") (class "Default")
      (node (ref "U4") (pin "A5") (pinfunction "NC_4_A5") (pintype "passive"))
    )
    (net (code "180") (name "unconnected-(U4-NC_5-PadK2)") (class "Default")
      (node (ref "U4") (pin "K2") (pinfunction "NC_5_K2") (pintype "passive"))
    )
    (net (code "181") (name "unconnected-(U4-NC_6-PadK3)") (class "Default")
      (node (ref "U4") (pin "K3") (pinfunction "NC_6_K3") (pintype "passive"))
    )
    (net (code "182") (name "unconnected-(U4-NC_7-PadK4)") (class "Default")
      (node (ref "U4") (pin "K4") (pinfunction "NC_7_K4") (pintype "passive"))
    )
    (net (code "183") (name "unconnected-(U4-NC_8-PadK5)") (class "Default")
      (node (ref "U4") (pin "K5") (pinfunction "NC_8_K5") (pintype "passive"))
    )
  )
)
